# esptoy_v123.net
KiCad netlist of a schematic drawn in EAGLE
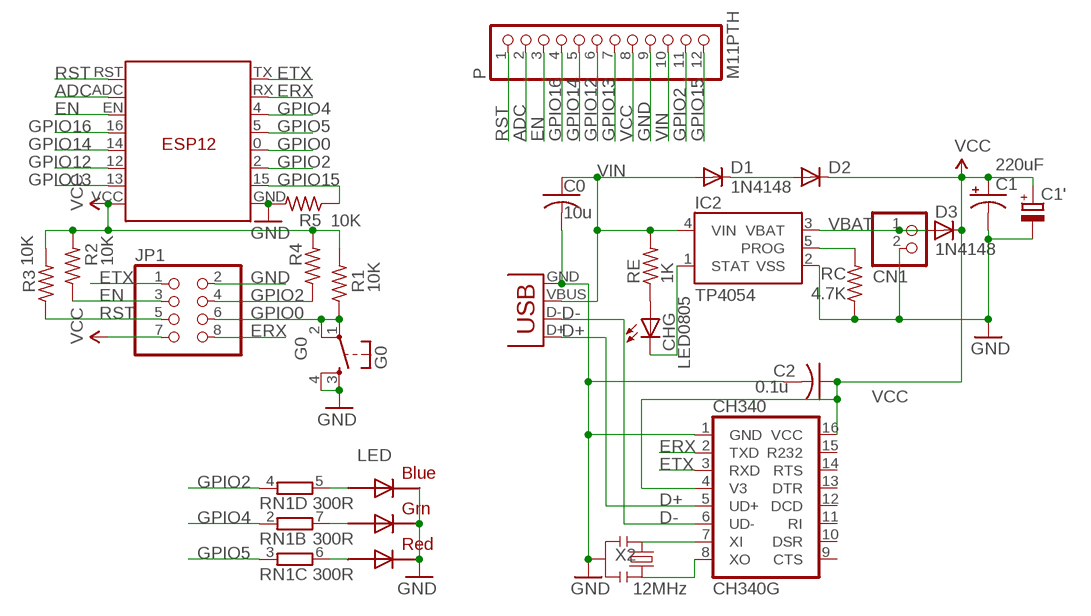
[diagram p0: schematic, sheet 1]

(export (version "E")
  (design (tool "Eeschema 10.0.6"))
  (components
    (comp (ref "C0")
      (value "10u")
      (footprint "eagle-import:C0805K")
      (libsource (lib "eagle-import") (part "adafruit2013_C-USC0805K"))
    )
    (comp (ref "C1")
      (value "220uF")
      (footprint "eagle-import:EIA3528-KIT")
      (libsource (lib "eagle-import") (part "CAP_POL3528-KIT"))
    )
    (comp (ref "C1'")
      (value "CPOL-EUD")
      (footprint "eagle-import:PANASONIC_D")
      (libsource (lib "eagle-import") (part "CPOL-EUD"))
    )
    (comp (ref "C2")
      (value "0.1u")
      (footprint "eagle-import:C0603K")
      (libsource (lib "eagle-import") (part "C-USC0603K"))
    )
    (comp (ref "CH340")
      (value "CH340G")
      (footprint "eagle-import:SO16")
      (libsource (lib "eagle-import") (part "CH340G"))
    )
    (comp (ref "CHG")
      (value "LED0805")
      (footprint "eagle-import:CHIPLED_0805")
      (libsource (lib "eagle-import") (part "LEDCHIPLED_0805"))
    )
    (comp (ref "CN1")
      (value "JST_2PIN-SMT-RA")
      (footprint "eagle-import:JST-PH-2-SMT-RA")
      (libsource (lib "eagle-import") (part "JST_2PIN-SMT-RA"))
    )
    (comp (ref "D1")
      (value "1N4148")
      (footprint "eagle-import:MINIMELF")
      (libsource (lib "eagle-import") (part "DIODE-MINIMELF"))
    )
    (comp (ref "D2")
      (value "DIODE-MINIMELF")
      (footprint "eagle-import:MINIMELF")
      (libsource (lib "eagle-import") (part "DIODE-MINIMELF"))
    )
    (comp (ref "D3")
      (value "1N4148")
      (footprint "eagle-import:MINIMELF")
      (libsource (lib "eagle-import") (part "DIODE-MINIMELF"))
    )
    (comp (ref "G0")
      (value "G0")
      (footprint "eagle-import:TACTILE_SWITCH_SMD")
      (libsource (lib "eagle-import") (part "TAC_SWITCHSMD"))
    )
    (comp (ref "IC2")
      (value "TP4054")
      (footprint "eagle-import:SOT23-5")
      (libsource (lib "eagle-import") (part "MCP73831"))
    )
    (comp (ref "JP1")
      (value "PINHD-2X4")
      (footprint "eagle-import:2X04")
      (libsource (lib "eagle-import") (part "PINHD-2X4"))
    )
    (comp (ref "LED")
      (value "RGBLED5050")
      (footprint "eagle-import:RGBLED5050")
      (libsource (lib "eagle-import") (part "RGBLED5050"))
    )
    (comp (ref "P")
      (value "M11PTH")
      (footprint "eagle-import:1X12-CB")
      (libsource (lib "eagle-import") (part "PINHD-1X12-CB"))
    )
    (comp (ref "R1")
      (value "10K")
      (footprint "eagle-import:R0603")
      (libsource (lib "eagle-import") (part "R-US_R0603"))
    )
    (comp (ref "R2")
      (value "10K")
      (footprint "eagle-import:R0603")
      (libsource (lib "eagle-import") (part "R-US_R0603"))
    )
    (comp (ref "R3")
      (value "10K")
      (footprint "eagle-import:R0603")
      (libsource (lib "eagle-import") (part "R-US_R0603"))
    )
    (comp (ref "R4")
      (value "R-US_R0603")
      (footprint "eagle-import:R0603")
      (libsource (lib "eagle-import") (part "R-US_R0603"))
    )
    (comp (ref "R5")
      (value "10K")
      (footprint "eagle-import:R0603")
      (libsource (lib "eagle-import") (part "R-US_R0603"))
    )
    (comp (ref "RC")
      (value "4.7K")
      (footprint "eagle-import:R0805")
      (libsource (lib "eagle-import") (part "adafruit2013_R-US_R0805"))
    )
    (comp (ref "RE")
      (value "1K")
      (footprint "eagle-import:R0603")
      (libsource (lib "eagle-import") (part "R-US_R0603"))
    )
    (comp (ref "RN1")
      (value "300R")
      (footprint "eagle-import:EXB38V")
      (libsource (lib "eagle-import") (part "4R-NEXB38V"))
    )
    (comp (ref "U$1")
      (value "ESP12")
      (footprint "eagle-import:ESP12")
      (libsource (lib "eagle-import") (part "ESP12"))
    )
    (comp (ref "X2")
      (value "12MHz")
      (footprint "eagle-import:RESONATOR-SMD")
      (libsource (lib "eagle-import") (part "RESONATORSMD"))
    )
    (comp (ref "X3")
      (value "USB-MICROB")
      (footprint "eagle-import:USB-MICROB")
      (libsource (lib "eagle-import") (part "USB-MICROB"))
    )
  )
  (nets
    (net (code "1") (name "/ADC") (class "Default")
      (node (ref "P") (pin "2") (pinfunction "2_2") (pintype "passive"))
      (node (ref "U$1") (pin "ADC") (pinfunction "ADC_ADC") (pintype "bidirectional"))
    )
    (net (code "2") (name "/D+") (class "Default")
      (node (ref "CH340") (pin "5") (pinfunction "UD+_5") (pintype "bidirectional"))
      (node (ref "X3") (pin "D+") (pinfunction "D+_D+") (pintype "bidirectional"))
    )
    (net (code "3") (name "/D-") (class "Default")
      (node (ref "CH340") (pin "6") (pinfunction "UD-_6") (pintype "bidirectional"))
      (node (ref "X3") (pin "D-") (pinfunction "D-_D-") (pintype "bidirectional"))
    )
    (net (code "4") (name "/EN") (class "Default")
      (node (ref "JP1") (pin "3") (pinfunction "3_3") (pintype "passive"))
      (node (ref "P") (pin "3") (pinfunction "3_3") (pintype "passive"))
      (node (ref "R2") (pin "1") (pinfunction "1_1") (pintype "passive"))
      (node (ref "U$1") (pin "EN") (pinfunction "EN_EN") (pintype "bidirectional"))
    )
    (net (code "5") (name "/ERX") (class "Default")
      (node (ref "CH340") (pin "2") (pinfunction "TXD_2") (pintype "bidirectional"))
      (node (ref "JP1") (pin "8") (pinfunction "8_8") (pintype "passive"))
      (node (ref "U$1") (pin "RX") (pinfunction "RX_RX") (pintype "bidirectional"))
    )
    (net (code "6") (name "/ETX") (class "Default")
      (node (ref "CH340") (pin "3") (pinfunction "RXD_3") (pintype "bidirectional"))
      (node (ref "JP1") (pin "1") (pinfunction "1_1") (pintype "passive"))
      (node (ref "U$1") (pin "TX") (pinfunction "TX_TX") (pintype "bidirectional"))
    )
    (net (code "7") (name "/GPIO0") (class "Default")
      (node (ref "G0") (pin "1") (pinfunction "1_1") (pintype "passive"))
      (node (ref "G0") (pin "2") (pinfunction "2_2") (pintype "passive"))
      (node (ref "JP1") (pin "6") (pinfunction "6_6") (pintype "passive"))
      (node (ref "R1") (pin "1") (pinfunction "1_1") (pintype "passive"))
      (node (ref "U$1") (pin "0") (pinfunction "G0_0") (pintype "bidirectional"))
    )
    (net (code "8") (name "/GPIO2") (class "Default")
      (node (ref "JP1") (pin "4") (pinfunction "4_4") (pintype "passive"))
      (node (ref "P") (pin "11") (pinfunction "11_11") (pintype "passive"))
      (node (ref "R4") (pin "1") (pinfunction "1_1") (pintype "passive"))
      (node (ref "RN1") (pin "4") (pinfunction "1_4") (pintype "passive"))
      (node (ref "U$1") (pin "2") (pinfunction "G2_2") (pintype "bidirectional"))
    )
    (net (code "9") (name "/GPIO4") (class "Default")
      (node (ref "RN1") (pin "2") (pinfunction "1_2") (pintype "passive"))
      (node (ref "U$1") (pin "4") (pinfunction "G4_4") (pintype "bidirectional"))
    )
    (net (code "10") (name "/GPIO5") (class "Default")
      (node (ref "RN1") (pin "3") (pinfunction "1_3") (pintype "passive"))
      (node (ref "U$1") (pin "5") (pinfunction "G5_5") (pintype "bidirectional"))
    )
    (net (code "11") (name "/GPIO12") (class "Default")
      (node (ref "P") (pin "6") (pinfunction "6_6") (pintype "passive"))
      (node (ref "U$1") (pin "12") (pinfunction "G12_12") (pintype "bidirectional"))
    )
    (net (code "12") (name "/GPIO13") (class "Default")
      (node (ref "P") (pin "7") (pinfunction "7_7") (pintype "passive"))
      (node (ref "U$1") (pin "13") (pinfunction "G13_13") (pintype "bidirectional"))
    )
    (net (code "13") (name "/GPIO14") (class "Default")
      (node (ref "P") (pin "5") (pinfunction "5_5") (pintype "passive"))
      (node (ref "U$1") (pin "14") (pinfunction "G14_14") (pintype "bidirectional"))
    )
    (net (code "14") (name "/GPIO15") (class "Default")
      (node (ref "P") (pin "12") (pinfunction "12_12") (pintype "passive"))
      (node (ref "R5") (pin "1") (pinfunction "1_1") (pintype "passive"))
      (node (ref "U$1") (pin "15") (pinfunction "G15_15") (pintype "bidirectional"))
    )
    (net (code "15") (name "/GPIO16") (class "Default")
      (node (ref "P") (pin "4") (pinfunction "4_4") (pintype "passive"))
      (node (ref "U$1") (pin "16") (pinfunction "G16_16") (pintype "bidirectional"))
    )
    (net (code "16") (name "/RST") (class "Default")
      (node (ref "JP1") (pin "5") (pinfunction "5_5") (pintype "passive"))
      (node (ref "P") (pin "1") (pinfunction "1_1") (pintype "passive"))
      (node (ref "R3") (pin "1") (pinfunction "1_1") (pintype "passive"))
      (node (ref "U$1") (pin "RST") (pinfunction "RST_RST") (pintype "bidirectional"))
    )
    (net (code "17") (name "/VBAT") (class "Default")
      (node (ref "CN1") (pin "1") (pinfunction "2_1") (pintype "passive"))
      (node (ref "D3") (pin "A") (pinfunction "A_A") (pintype "passive"))
      (node (ref "IC2") (pin "3") (pinfunction "VBAT_3") (pintype "power_in"))
    )
    (net (code "18") (name "/VIN") (class "Default")
      (node (ref "C0") (pin "1") (pinfunction "1_1") (pintype "passive"))
      (node (ref "D1") (pin "A") (pinfunction "A_A") (pintype "passive"))
      (node (ref "IC2") (pin "4") (pinfunction "VIN_4") (pintype "power_in"))
      (node (ref "P") (pin "10") (pinfunction "10_10") (pintype "passive"))
      (node (ref "RE") (pin "2") (pinfunction "2_2") (pintype "passive"))
      (node (ref "X3") (pin "VBUS") (pinfunction "VBUS_VBUS") (pintype "bidirectional"))
    )
    (net (code "19") (name "GND") (class "Default")
      (node (ref "C0") (pin "2") (pinfunction "2_2") (pintype "passive"))
      (node (ref "C1") (pin "C") (pinfunction "-_C") (pintype "passive"))
      (node (ref "C1'") (pin "-") (pinfunction "-_-") (pintype "passive"))
      (node (ref "C2") (pin "2") (pinfunction "2_2") (pintype "passive"))
      (node (ref "CH340") (pin "1") (pinfunction "GND_1") (pintype "power_in"))
      (node (ref "CN1") (pin "2") (pinfunction "1_2") (pintype "passive"))
      (node (ref "G0") (pin "3") (pinfunction "3_3") (pintype "passive"))
      (node (ref "G0") (pin "4") (pinfunction "4_4") (pintype "passive"))
      (node (ref "IC2") (pin "2") (pinfunction "VSS_2") (pintype "power_in"))
      (node (ref "JP1") (pin "2") (pinfunction "2_2") (pintype "passive"))
      (node (ref "LED") (pin "4") (pinfunction "BLUE_C_4") (pintype "bidirectional"))
      (node (ref "LED") (pin "5") (pinfunction "RED_C_5") (pintype "bidirectional"))
      (node (ref "LED") (pin "6") (pinfunction "GREEN_C_6") (pintype "bidirectional"))
      (node (ref "P") (pin "9") (pinfunction "9_9") (pintype "passive"))
      (node (ref "R5") (pin "2") (pinfunction "2_2") (pintype "passive"))
      (node (ref "RC") (pin "1") (pinfunction "1_1") (pintype "passive"))
      (node (ref "U$1") (pin "GND") (pinfunction "GND_GND") (pintype "power_in"))
      (node (ref "X2") (pin "2") (pinfunction "2_2") (pintype "passive"))
      (node (ref "X3") (pin "GND") (pinfunction "GND_GND") (pintype "bidirectional"))
    )
    (net (code "20") (name "Net-(CH340-XI)") (class "Default")
      (node (ref "CH340") (pin "7") (pinfunction "XI_7") (pintype "bidirectional"))
      (node (ref "X2") (pin "1") (pinfunction "1_1") (pintype "passive"))
    )
    (net (code "21") (name "Net-(CH340-XO)") (class "Default")
      (node (ref "CH340") (pin "8") (pinfunction "XO_8") (pintype "bidirectional"))
      (node (ref "X2") (pin "3") (pinfunction "3_3") (pintype "passive"))
    )
    (net (code "22") (name "Net-(CHG-PadA)") (class "Default")
      (node (ref "CHG") (pin "A") (pinfunction "A_A") (pintype "passive"))
      (node (ref "RE") (pin "1") (pinfunction "1_1") (pintype "passive"))
    )
    (net (code "23") (name "Net-(D1-PadC)") (class "Default")
      (node (ref "D1") (pin "C") (pinfunction "C_C") (pintype "passive"))
      (node (ref "D2") (pin "A") (pinfunction "A_A") (pintype "passive"))
    )
    (net (code "24") (name "Net-(IC2-PROG)") (class "Default")
      (node (ref "IC2") (pin "5") (pinfunction "PROG_5") (pintype "input"))
      (node (ref "RC") (pin "2") (pinfunction "2_2") (pintype "passive"))
    )
    (net (code "25") (name "Net-(IC2-STAT)") (class "Default")
      (node (ref "CHG") (pin "C") (pinfunction "C_C") (pintype "passive"))
      (node (ref "IC2") (pin "1") (pinfunction "STAT_1") (pintype "output"))
    )
    (net (code "26") (name "Net-(LED-BLUE_A)") (class "Default")
      (node (ref "LED") (pin "3") (pinfunction "BLUE_A_3") (pintype "bidirectional"))
      (node (ref "RN1") (pin "5") (pinfunction "2_5") (pintype "passive"))
    )
    (net (code "27") (name "Net-(LED-GREEN_A)") (class "Default")
      (node (ref "LED") (pin "1") (pinfunction "GREEN_A_1") (pintype "bidirectional"))
      (node (ref "RN1") (pin "7") (pinfunction "2_7") (pintype "passive"))
    )
    (net (code "28") (name "Net-(LED-RED_A)") (class "Default")
      (node (ref "LED") (pin "2") (pinfunction "RED_A_2") (pintype "bidirectional"))
      (node (ref "RN1") (pin "6") (pinfunction "2_6") (pintype "passive"))
    )
    (net (code "29") (name "VCC") (class "Default")
      (node (ref "C1") (pin "A") (pinfunction "+_A") (pintype "passive"))
      (node (ref "C1'") (pin "+") (pinfunction "+_+") (pintype "passive"))
      (node (ref "C2") (pin "1") (pinfunction "1_1") (pintype "passive"))
      (node (ref "CH340") (pin "16") (pinfunction "VCC_16") (pintype "power_in"))
      (node (ref "CH340") (pin "4") (pinfunction "V3_4") (pintype "bidirectional"))
      (node (ref "D2") (pin "C") (pinfunction "C_C") (pintype "passive"))
      (node (ref "D3") (pin "C") (pinfunction "C_C") (pintype "passive"))
      (node (ref "JP1") (pin "7") (pinfunction "7_7") (pintype "passive"))
      (node (ref "P") (pin "8") (pinfunction "8_8") (pintype "passive"))
      (node (ref "R1") (pin "2") (pinfunction "2_2") (pintype "passive"))
      (node (ref "R2") (pin "2") (pinfunction "2_2") (pintype "passive"))
      (node (ref "R3") (pin "2") (pinfunction "2_2") (pintype "passive"))
      (node (ref "R4") (pin "2") (pinfunction "2_2") (pintype "passive"))
      (node (ref "U$1") (pin "VCC") (pinfunction "VCC_VCC") (pintype "power_in"))
    )
    (net (code "30") (name "unconnected-(CH340-CTS-Pad9)") (class "Default")
      (node (ref "CH340") (pin "9") (pinfunction "CTS_9") (pintype "bidirectional"))
    )
    (net (code "31") (name "unconnected-(CH340-DCD-Pad12)") (class "Default")
      (node (ref "CH340") (pin "12") (pinfunction "DCD_12") (pintype "bidirectional"))
    )
    (net (code "32") (name "unconnected-(CH340-DSR-Pad10)") (class "Default")
      (node (ref "CH340") (pin "10") (pinfunction "DSR_10") (pintype "bidirectional"))
    )
    (net (code "33") (name "unconnected-(CH340-DTR-Pad13)") (class "Default")
      (node (ref "CH340") (pin "13") (pinfunction "DTR_13") (pintype "bidirectional"))
    )
    (net (code "34") (name "unconnected-(CH340-R232-Pad15)") (class "Default")
      (node (ref "CH340") (pin "15") (pinfunction "R232_15") (pintype "bidirectional"))
    )
    (net (code "35") (name "unconnected-(CH340-RI-Pad11)") (class "Default")
      (node (ref "CH340") (pin "11") (pinfunction "RI_11") (pintype "bidirectional"))
    )
    (net (code "36") (name "unconnected-(CH340-RTS-Pad14)") (class "Default")
      (node (ref "CH340") (pin "14") (pinfunction "RTS_14") (pintype "bidirectional"))
    )
  )
)
